# 2_matrix.net
KiCad netlist of a schematic drawn in Altium Designer
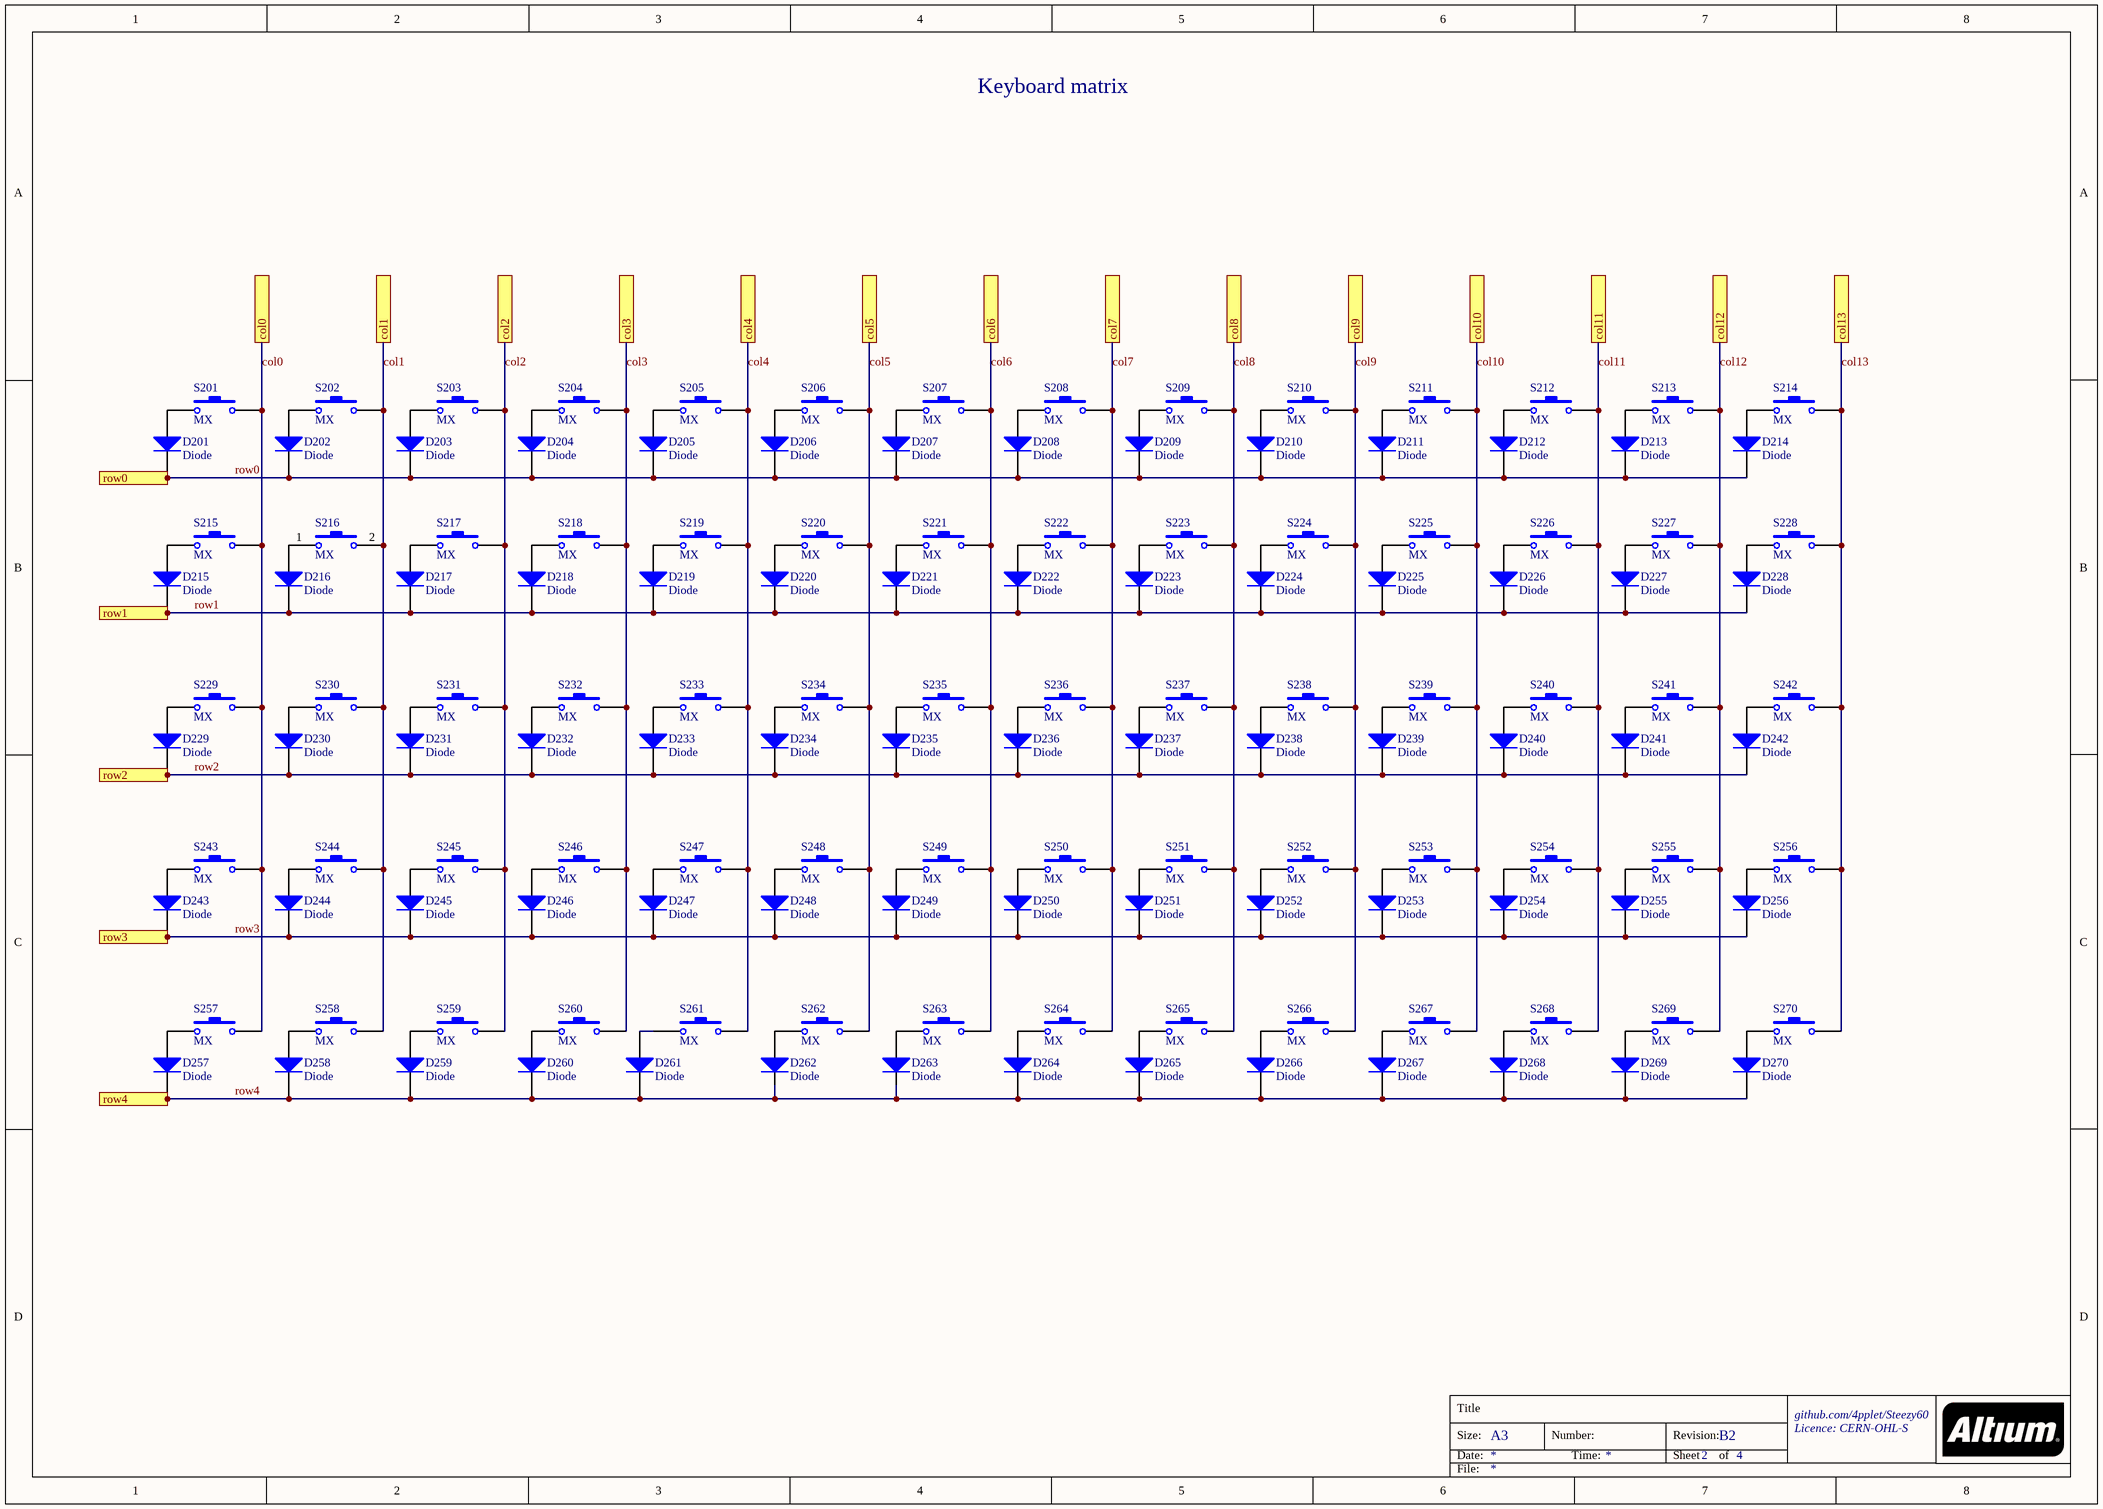
[diagram p0: 2_matrix.SchDoc]

(export (version "E")
  (design (tool "Eeschema 10.0.6"))
  (components
    (comp (ref "D201")
      (value "Diode")
      (footprint "SOD-123")
      (description "Default Diode")
      (fields (field (name "LCSC PART #") "C81598") (field (name "MRF.PART") "1N4148W"))
      (libsource (lib "Miscellaneous Devices") (part "Diode"))
    )
    (comp (ref "D202")
      (value "Diode")
      (footprint "SOD-123")
      (description "Default Diode")
      (fields (field (name "LCSC PART #") "C81598") (field (name "MRF.PART") "1N4148W"))
      (libsource (lib "Miscellaneous Devices") (part "Diode"))
    )
    (comp (ref "D203")
      (value "Diode")
      (footprint "SOD-123")
      (description "Default Diode")
      (fields (field (name "LCSC PART #") "C81598") (field (name "MRF.PART") "1N4148W"))
      (libsource (lib "Miscellaneous Devices") (part "Diode"))
    )
    (comp (ref "D204")
      (value "Diode")
      (footprint "SOD-123")
      (description "Default Diode")
      (fields (field (name "LCSC PART #") "C81598") (field (name "MRF.PART") "1N4148W"))
      (libsource (lib "Miscellaneous Devices") (part "Diode"))
    )
    (comp (ref "D205")
      (value "Diode")
      (footprint "SOD-123")
      (description "Default Diode")
      (fields (field (name "LCSC PART #") "C81598") (field (name "MRF.PART") "1N4148W"))
      (libsource (lib "Miscellaneous Devices") (part "Diode"))
    )
    (comp (ref "D206")
      (value "Diode")
      (footprint "SOD-123")
      (description "Default Diode")
      (fields (field (name "LCSC PART #") "C81598") (field (name "MRF.PART") "1N4148W"))
      (libsource (lib "Miscellaneous Devices") (part "Diode"))
    )
    (comp (ref "D207")
      (value "Diode")
      (footprint "SOD-123")
      (description "Default Diode")
      (fields (field (name "LCSC PART #") "C81598") (field (name "MRF.PART") "1N4148W"))
      (libsource (lib "Miscellaneous Devices") (part "Diode"))
    )
    (comp (ref "D208")
      (value "Diode")
      (footprint "SOD-123")
      (description "Default Diode")
      (fields (field (name "LCSC PART #") "C81598") (field (name "MRF.PART") "1N4148W"))
      (libsource (lib "Miscellaneous Devices") (part "Diode"))
    )
    (comp (ref "D209")
      (value "Diode")
      (footprint "SOD-123")
      (description "Default Diode")
      (fields (field (name "LCSC PART #") "C81598") (field (name "MRF.PART") "1N4148W"))
      (libsource (lib "Miscellaneous Devices") (part "Diode"))
    )
    (comp (ref "D210")
      (value "Diode")
      (footprint "SOD-123")
      (description "Default Diode")
      (fields (field (name "LCSC PART #") "C81598") (field (name "MRF.PART") "1N4148W"))
      (libsource (lib "Miscellaneous Devices") (part "Diode"))
    )
    (comp (ref "D211")
      (value "Diode")
      (footprint "SOD-123")
      (description "Default Diode")
      (fields (field (name "LCSC PART #") "C81598") (field (name "MRF.PART") "1N4148W"))
      (libsource (lib "Miscellaneous Devices") (part "Diode"))
    )
    (comp (ref "D212")
      (value "Diode")
      (footprint "SOD-123")
      (description "Default Diode")
      (fields (field (name "LCSC PART #") "C81598") (field (name "MRF.PART") "1N4148W"))
      (libsource (lib "Miscellaneous Devices") (part "Diode"))
    )
    (comp (ref "D213")
      (value "Diode")
      (footprint "SOD-123")
      (description "Default Diode")
      (fields (field (name "LCSC PART #") "C81598") (field (name "MRF.PART") "1N4148W"))
      (libsource (lib "Miscellaneous Devices") (part "Diode"))
    )
    (comp (ref "D214")
      (value "Diode")
      (footprint "SOD-123")
      (description "Default Diode")
      (fields (field (name "LCSC PART #") "C81598") (field (name "MRF.PART") "1N4148W"))
      (libsource (lib "Miscellaneous Devices") (part "Diode"))
    )
    (comp (ref "D215")
      (value "Diode")
      (footprint "SOD-123")
      (description "Default Diode")
      (fields (field (name "LCSC PART #") "C81598") (field (name "MRF.PART") "1N4148W"))
      (libsource (lib "Miscellaneous Devices") (part "Diode"))
    )
    (comp (ref "D216")
      (value "Diode")
      (footprint "SOD-123")
      (description "Default Diode")
      (fields (field (name "LCSC PART #") "C81598") (field (name "MRF.PART") "1N4148W"))
      (libsource (lib "Miscellaneous Devices") (part "Diode"))
    )
    (comp (ref "D217")
      (value "Diode")
      (footprint "SOD-123")
      (description "Default Diode")
      (fields (field (name "LCSC PART #") "C81598") (field (name "MRF.PART") "1N4148W"))
      (libsource (lib "Miscellaneous Devices") (part "Diode"))
    )
    (comp (ref "D218")
      (value "Diode")
      (footprint "SOD-123")
      (description "Default Diode")
      (fields (field (name "LCSC PART #") "C81598") (field (name "MRF.PART") "1N4148W"))
      (libsource (lib "Miscellaneous Devices") (part "Diode"))
    )
    (comp (ref "D219")
      (value "Diode")
      (footprint "SOD-123")
      (description "Default Diode")
      (fields (field (name "LCSC PART #") "C81598") (field (name "MRF.PART") "1N4148W"))
      (libsource (lib "Miscellaneous Devices") (part "Diode"))
    )
    (comp (ref "D220")
      (value "Diode")
      (footprint "SOD-123")
      (description "Default Diode")
      (fields (field (name "LCSC PART #") "C81598") (field (name "MRF.PART") "1N4148W"))
      (libsource (lib "Miscellaneous Devices") (part "Diode"))
    )
    (comp (ref "D221")
      (value "Diode")
      (footprint "SOD-123")
      (description "Default Diode")
      (fields (field (name "LCSC PART #") "C81598") (field (name "MRF.PART") "1N4148W"))
      (libsource (lib "Miscellaneous Devices") (part "Diode"))
    )
    (comp (ref "D222")
      (value "Diode")
      (footprint "SOD-123")
      (description "Default Diode")
      (fields (field (name "LCSC PART #") "C81598") (field (name "MRF.PART") "1N4148W"))
      (libsource (lib "Miscellaneous Devices") (part "Diode"))
    )
    (comp (ref "D223")
      (value "Diode")
      (footprint "SOD-123")
      (description "Default Diode")
      (fields (field (name "LCSC PART #") "C81598") (field (name "MRF.PART") "1N4148W"))
      (libsource (lib "Miscellaneous Devices") (part "Diode"))
    )
    (comp (ref "D224")
      (value "Diode")
      (footprint "SOD-123")
      (description "Default Diode")
      (fields (field (name "LCSC PART #") "C81598") (field (name "MRF.PART") "1N4148W"))
      (libsource (lib "Miscellaneous Devices") (part "Diode"))
    )
    (comp (ref "D225")
      (value "Diode")
      (footprint "SOD-123")
      (description "Default Diode")
      (fields (field (name "LCSC PART #") "C81598") (field (name "MRF.PART") "1N4148W"))
      (libsource (lib "Miscellaneous Devices") (part "Diode"))
    )
    (comp (ref "D226")
      (value "Diode")
      (footprint "SOD-123")
      (description "Default Diode")
      (fields (field (name "LCSC PART #") "C81598") (field (name "MRF.PART") "1N4148W"))
      (libsource (lib "Miscellaneous Devices") (part "Diode"))
    )
    (comp (ref "D227")
      (value "Diode")
      (footprint "SOD-123")
      (description "Default Diode")
      (fields (field (name "LCSC PART #") "C81598") (field (name "MRF.PART") "1N4148W"))
      (libsource (lib "Miscellaneous Devices") (part "Diode"))
    )
    (comp (ref "D228")
      (value "Diode")
      (footprint "SOD-123")
      (description "Default Diode")
      (fields (field (name "LCSC PART #") "C81598") (field (name "MRF.PART") "1N4148W"))
      (libsource (lib "Miscellaneous Devices") (part "Diode"))
    )
    (comp (ref "D229")
      (value "Diode")
      (footprint "SOD-123")
      (description "Default Diode")
      (fields (field (name "LCSC PART #") "C81598") (field (name "MRF.PART") "1N4148W"))
      (libsource (lib "Miscellaneous Devices") (part "Diode"))
    )
    (comp (ref "D230")
      (value "Diode")
      (footprint "SOD-123")
      (description "Default Diode")
      (fields (field (name "LCSC PART #") "C81598") (field (name "MRF.PART") "1N4148W"))
      (libsource (lib "Miscellaneous Devices") (part "Diode"))
    )
    (comp (ref "D231")
      (value "Diode")
      (footprint "SOD-123")
      (description "Default Diode")
      (fields (field (name "LCSC PART #") "C81598") (field (name "MRF.PART") "1N4148W"))
      (libsource (lib "Miscellaneous Devices") (part "Diode"))
    )
    (comp (ref "D232")
      (value "Diode")
      (footprint "SOD-123")
      (description "Default Diode")
      (fields (field (name "LCSC PART #") "C81598") (field (name "MRF.PART") "1N4148W"))
      (libsource (lib "Miscellaneous Devices") (part "Diode"))
    )
    (comp (ref "D233")
      (value "Diode")
      (footprint "SOD-123")
      (description "Default Diode")
      (fields (field (name "LCSC PART #") "C81598") (field (name "MRF.PART") "1N4148W"))
      (libsource (lib "Miscellaneous Devices") (part "Diode"))
    )
    (comp (ref "D234")
      (value "Diode")
      (footprint "SOD-123")
      (description "Default Diode")
      (fields (field (name "LCSC PART #") "C81598") (field (name "MRF.PART") "1N4148W"))
      (libsource (lib "Miscellaneous Devices") (part "Diode"))
    )
    (comp (ref "D235")
      (value "Diode")
      (footprint "SOD-123")
      (description "Default Diode")
      (fields (field (name "LCSC PART #") "C81598") (field (name "MRF.PART") "1N4148W"))
      (libsource (lib "Miscellaneous Devices") (part "Diode"))
    )
    (comp (ref "D236")
      (value "Diode")
      (footprint "SOD-123")
      (description "Default Diode")
      (fields (field (name "LCSC PART #") "C81598") (field (name "MRF.PART") "1N4148W"))
      (libsource (lib "Miscellaneous Devices") (part "Diode"))
    )
    (comp (ref "D237")
      (value "Diode")
      (footprint "SOD-123")
      (description "Default Diode")
      (fields (field (name "LCSC PART #") "C81598") (field (name "MRF.PART") "1N4148W"))
      (libsource (lib "Miscellaneous Devices") (part "Diode"))
    )
    (comp (ref "D238")
      (value "Diode")
      (footprint "SOD-123")
      (description "Default Diode")
      (fields (field (name "LCSC PART #") "C81598") (field (name "MRF.PART") "1N4148W"))
      (libsource (lib "Miscellaneous Devices") (part "Diode"))
    )
    (comp (ref "D239")
      (value "Diode")
      (footprint "SOD-123")
      (description "Default Diode")
      (fields (field (name "LCSC PART #") "C81598") (field (name "MRF.PART") "1N4148W"))
      (libsource (lib "Miscellaneous Devices") (part "Diode"))
    )
    (comp (ref "D240")
      (value "Diode")
      (footprint "SOD-123")
      (description "Default Diode")
      (fields (field (name "LCSC PART #") "C81598") (field (name "MRF.PART") "1N4148W"))
      (libsource (lib "Miscellaneous Devices") (part "Diode"))
    )
    (comp (ref "D241")
      (value "Diode")
      (footprint "SOD-123")
      (description "Default Diode")
      (fields (field (name "LCSC PART #") "C81598") (field (name "MRF.PART") "1N4148W"))
      (libsource (lib "Miscellaneous Devices") (part "Diode"))
    )
    (comp (ref "D242")
      (value "Diode")
      (footprint "SOD-123")
      (description "Default Diode")
      (fields (field (name "LCSC PART #") "C81598") (field (name "MRF.PART") "1N4148W"))
      (libsource (lib "Miscellaneous Devices") (part "Diode"))
    )
    (comp (ref "D243")
      (value "Diode")
      (footprint "SOD-123")
      (description "Default Diode")
      (fields (field (name "LCSC PART #") "C81598") (field (name "MRF.PART") "1N4148W"))
      (libsource (lib "Miscellaneous Devices") (part "Diode"))
    )
    (comp (ref "D244")
      (value "Diode")
      (footprint "SOD-123")
      (description "Default Diode")
      (fields (field (name "LCSC PART #") "C81598") (field (name "MRF.PART") "1N4148W"))
      (libsource (lib "Miscellaneous Devices") (part "Diode"))
    )
    (comp (ref "D245")
      (value "Diode")
      (footprint "SOD-123")
      (description "Default Diode")
      (fields (field (name "LCSC PART #") "C81598") (field (name "MRF.PART") "1N4148W"))
      (libsource (lib "Miscellaneous Devices") (part "Diode"))
    )
    (comp (ref "D246")
      (value "Diode")
      (footprint "SOD-123")
      (description "Default Diode")
      (fields (field (name "LCSC PART #") "C81598") (field (name "MRF.PART") "1N4148W"))
      (libsource (lib "Miscellaneous Devices") (part "Diode"))
    )
    (comp (ref "D247")
      (value "Diode")
      (footprint "SOD-123")
      (description "Default Diode")
      (fields (field (name "LCSC PART #") "C81598") (field (name "MRF.PART") "1N4148W"))
      (libsource (lib "Miscellaneous Devices") (part "Diode"))
    )
    (comp (ref "D248")
      (value "Diode")
      (footprint "SOD-123")
      (description "Default Diode")
      (fields (field (name "LCSC PART #") "C81598") (field (name "MRF.PART") "1N4148W"))
      (libsource (lib "Miscellaneous Devices") (part "Diode"))
    )
    (comp (ref "D249")
      (value "Diode")
      (footprint "SOD-123")
      (description "Default Diode")
      (fields (field (name "LCSC PART #") "C81598") (field (name "MRF.PART") "1N4148W"))
      (libsource (lib "Miscellaneous Devices") (part "Diode"))
    )
    (comp (ref "D250")
      (value "Diode")
      (footprint "SOD-123")
      (description "Default Diode")
      (fields (field (name "LCSC PART #") "C81598") (field (name "MRF.PART") "1N4148W"))
      (libsource (lib "Miscellaneous Devices") (part "Diode"))
    )
    (comp (ref "D251")
      (value "Diode")
      (footprint "SOD-123")
      (description "Default Diode")
      (fields (field (name "LCSC PART #") "C81598") (field (name "MRF.PART") "1N4148W"))
      (libsource (lib "Miscellaneous Devices") (part "Diode"))
    )
    (comp (ref "D252")
      (value "Diode")
      (footprint "SOD-123")
      (description "Default Diode")
      (fields (field (name "LCSC PART #") "C81598") (field (name "MRF.PART") "1N4148W"))
      (libsource (lib "Miscellaneous Devices") (part "Diode"))
    )
    (comp (ref "D253")
      (value "Diode")
      (footprint "SOD-123")
      (description "Default Diode")
      (fields (field (name "LCSC PART #") "C81598") (field (name "MRF.PART") "1N4148W"))
      (libsource (lib "Miscellaneous Devices") (part "Diode"))
    )
    (comp (ref "D254")
      (value "Diode")
      (footprint "SOD-123")
      (description "Default Diode")
      (fields (field (name "LCSC PART #") "C81598") (field (name "MRF.PART") "1N4148W"))
      (libsource (lib "Miscellaneous Devices") (part "Diode"))
    )
    (comp (ref "D255")
      (value "Diode")
      (footprint "SOD-123")
      (description "Default Diode")
      (fields (field (name "LCSC PART #") "C81598") (field (name "MRF.PART") "1N4148W"))
      (libsource (lib "Miscellaneous Devices") (part "Diode"))
    )
    (comp (ref "D256")
      (value "Diode")
      (footprint "SOD-123")
      (description "Default Diode")
      (fields (field (name "LCSC PART #") "C81598") (field (name "MRF.PART") "1N4148W"))
      (libsource (lib "Miscellaneous Devices") (part "Diode"))
    )
    (comp (ref "D257")
      (value "Diode")
      (footprint "SOD-123")
      (description "Default Diode")
      (fields (field (name "LCSC PART #") "C81598") (field (name "MRF.PART") "1N4148W"))
      (libsource (lib "Miscellaneous Devices") (part "Diode"))
    )
    (comp (ref "D258")
      (value "Diode")
      (footprint "SOD-123")
      (description "Default Diode")
      (fields (field (name "LCSC PART #") "C81598") (field (name "MRF.PART") "1N4148W"))
      (libsource (lib "Miscellaneous Devices") (part "Diode"))
    )
    (comp (ref "D259")
      (value "Diode")
      (footprint "SOD-123")
      (description "Default Diode")
      (fields (field (name "LCSC PART #") "C81598") (field (name "MRF.PART") "1N4148W"))
      (libsource (lib "Miscellaneous Devices") (part "Diode"))
    )
    (comp (ref "D260")
      (value "Diode")
      (footprint "SOD-123")
      (description "Default Diode")
      (fields (field (name "LCSC PART #") "C81598") (field (name "MRF.PART") "1N4148W"))
      (libsource (lib "Miscellaneous Devices") (part "Diode"))
    )
    (comp (ref "D261")
      (value "Diode")
      (footprint "SOD-123")
      (description "Default Diode")
      (fields (field (name "LCSC PART #") "C81598") (field (name "MRF.PART") "1N4148W"))
      (libsource (lib "Miscellaneous Devices") (part "Diode"))
    )
    (comp (ref "D262")
      (value "Diode")
      (footprint "SOD-123")
      (description "Default Diode")
      (fields (field (name "LCSC PART #") "C81598") (field (name "MRF.PART") "1N4148W"))
      (libsource (lib "Miscellaneous Devices") (part "Diode"))
    )
    (comp (ref "D263")
      (value "Diode")
      (footprint "SOD-123")
      (description "Default Diode")
      (fields (field (name "LCSC PART #") "C81598") (field (name "MRF.PART") "1N4148W"))
      (libsource (lib "Miscellaneous Devices") (part "Diode"))
    )
    (comp (ref "D264")
      (value "Diode")
      (footprint "SOD-123")
      (description "Default Diode")
      (fields (field (name "LCSC PART #") "C81598") (field (name "MRF.PART") "1N4148W"))
      (libsource (lib "Miscellaneous Devices") (part "Diode"))
    )
    (comp (ref "D265")
      (value "Diode")
      (footprint "SOD-123")
      (description "Default Diode")
      (fields (field (name "LCSC PART #") "C81598") (field (name "MRF.PART") "1N4148W"))
      (libsource (lib "Miscellaneous Devices") (part "Diode"))
    )
    (comp (ref "D266")
      (value "Diode")
      (footprint "SOD-123")
      (description "Default Diode")
      (fields (field (name "LCSC PART #") "C81598") (field (name "MRF.PART") "1N4148W"))
      (libsource (lib "Miscellaneous Devices") (part "Diode"))
    )
    (comp (ref "D267")
      (value "Diode")
      (footprint "SOD-123")
      (description "Default Diode")
      (fields (field (name "LCSC PART #") "C81598") (field (name "MRF.PART") "1N4148W"))
      (libsource (lib "Miscellaneous Devices") (part "Diode"))
    )
    (comp (ref "D268")
      (value "Diode")
      (footprint "SOD-123")
      (description "Default Diode")
      (fields (field (name "LCSC PART #") "C81598") (field (name "MRF.PART") "1N4148W"))
      (libsource (lib "Miscellaneous Devices") (part "Diode"))
    )
    (comp (ref "D269")
      (value "Diode")
      (footprint "SOD-123")
      (description "Default Diode")
      (fields (field (name "LCSC PART #") "C81598") (field (name "MRF.PART") "1N4148W"))
      (libsource (lib "Miscellaneous Devices") (part "Diode"))
    )
    (comp (ref "D270")
      (value "Diode")
      (footprint "SOD-123")
      (description "Default Diode")
      (fields (field (name "LCSC PART #") "C81598") (field (name "MRF.PART") "1N4148W"))
      (libsource (lib "Miscellaneous Devices") (part "Diode"))
    )
    (comp (ref "S201")
      (value "MX")
      (footprint "Alps-switch - switched pol")
      (description "Switch")
      (libsource (lib "Miscellaneous Devices") (part "SW-PB"))
    )
    (comp (ref "S202")
      (value "MX")
      (footprint "Alps-switch - switched pol")
      (description "Switch")
      (libsource (lib "Miscellaneous Devices") (part "SW-PB"))
    )
    (comp (ref "S203")
      (value "MX")
      (footprint "Alps-switch - switched pol")
      (description "Switch")
      (libsource (lib "Miscellaneous Devices") (part "SW-PB"))
    )
    (comp (ref "S204")
      (value "MX")
      (footprint "Alps-switch - switched pol")
      (description "Switch")
      (libsource (lib "Miscellaneous Devices") (part "SW-PB"))
    )
    (comp (ref "S205")
      (value "MX")
      (footprint "Alps-switch - switched pol")
      (description "Switch")
      (libsource (lib "Miscellaneous Devices") (part "SW-PB"))
    )
    (comp (ref "S206")
      (value "MX")
      (footprint "Alps-switch - switched pol")
      (description "Switch")
      (libsource (lib "Miscellaneous Devices") (part "SW-PB"))
    )
    (comp (ref "S207")
      (value "MX")
      (footprint "Alps-switch - switched pol")
      (description "Switch")
      (libsource (lib "Miscellaneous Devices") (part "SW-PB"))
    )
    (comp (ref "S208")
      (value "MX")
      (footprint "Alps-switch - switched pol")
      (description "Switch")
      (libsource (lib "Miscellaneous Devices") (part "SW-PB"))
    )
    (comp (ref "S209")
      (value "MX")
      (footprint "Alps-switch")
      (description "Switch")
      (libsource (lib "Miscellaneous Devices") (part "SW-PB"))
    )
    (comp (ref "S210")
      (value "MX")
      (footprint "Alps-switch")
      (description "Switch")
      (libsource (lib "Miscellaneous Devices") (part "SW-PB"))
    )
    (comp (ref "S211")
      (value "MX")
      (footprint "Alps-switch")
      (description "Switch")
      (libsource (lib "Miscellaneous Devices") (part "SW-PB"))
    )
    (comp (ref "S212")
      (value "MX")
      (footprint "Alps-switch")
      (description "Switch")
      (libsource (lib "Miscellaneous Devices") (part "SW-PB"))
    )
    (comp (ref "S213")
      (value "MX")
      (footprint "Alps-switch")
      (description "Switch")
      (libsource (lib "Miscellaneous Devices") (part "SW-PB"))
    )
    (comp (ref "S214")
      (value "MX")
      (footprint "ALPS-SWITCH - FLAT PIN1")
      (description "Switch")
      (libsource (lib "Miscellaneous Devices") (part "SW-PB"))
    )
    (comp (ref "S215")
      (value "MX")
      (footprint "ALPS-switch - 1.25U - switched pol")
      (description "TAB")
      (libsource (lib "Miscellaneous Devices") (part "SW-PB"))
    )
    (comp (ref "S216")
      (value "MX")
      (footprint "Alps-switch")
      (description "Switch")
      (libsource (lib "") (part "SW-PB_1"))
    )
    (comp (ref "S217")
      (value "MX")
      (footprint "Alps-switch - switched pol")
      (description "Switch")
      (libsource (lib "Miscellaneous Devices") (part "SW-PB"))
    )
    (comp (ref "S218")
      (value "MX")
      (footprint "Alps-switch - switched pol")
      (description "Switch")
      (libsource (lib "Miscellaneous Devices") (part "SW-PB"))
    )
    (comp (ref "S219")
      (value "MX")
      (footprint "Alps-switch - switched pol")
      (description "Switch")
      (libsource (lib "Miscellaneous Devices") (part "SW-PB"))
    )
    (comp (ref "S220")
      (value "MX")
      (footprint "Alps-switch - switched pol")
      (description "Switch")
      (libsource (lib "Miscellaneous Devices") (part "SW-PB"))
    )
    (comp (ref "S221")
      (value "MX")
      (footprint "Alps-switch - switched pol")
      (description "Switch")
      (libsource (lib "Miscellaneous Devices") (part "SW-PB"))
    )
    (comp (ref "S222")
      (value "MX")
      (footprint "Alps-switch - switched pol")
      (description "Switch")
      (libsource (lib "Miscellaneous Devices") (part "SW-PB"))
    )
    (comp (ref "S223")
      (value "MX")
      (footprint "Alps-switch - switched pol")
      (description "Switch")
      (libsource (lib "Miscellaneous Devices") (part "SW-PB"))
    )
    (comp (ref "S224")
      (value "MX")
      (footprint "Alps-switch - switched pol")
      (description "Switch")
      (libsource (lib "Miscellaneous Devices") (part "SW-PB"))
    )
    (comp (ref "S225")
      (value "MX")
      (footprint "Alps-switch")
      (description "Switch")
      (libsource (lib "Miscellaneous Devices") (part "SW-PB"))
    )
    (comp (ref "S226")
      (value "MX")
      (footprint "Alps-switch")
      (description "Switch")
      (libsource (lib "Miscellaneous Devices") (part "SW-PB"))
    )
    (comp (ref "S227")
      (value "MX")
      (footprint "ALPS-switch - offset-R")
      (description "Switch")
      (libsource (lib "Miscellaneous Devices") (part "SW-PB"))
    )
    (comp (ref "S228")
      (value "MX")
      (footprint "ALPS-switch - 1.5U")
      (description "Switch")
      (libsource (lib "Miscellaneous Devices") (part "SW-PB"))
    )
    (comp (ref "S229")
      (value "MX")
      (footprint "ALPS-switch - CAPS")
      (description "Switch")
      (libsource (lib "Miscellaneous Devices") (part "SW-PB"))
    )
    (comp (ref "S230")
      (value "MX")
      (footprint "Alps-switch")
      (description "Switch")
      (libsource (lib "Miscellaneous Devices") (part "SW-PB"))
    )
    (comp (ref "S231")
      (value "MX")
      (footprint "Alps-switch - switched pol")
      (description "Switch")
      (libsource (lib "Miscellaneous Devices") (part "SW-PB"))
    )
    (comp (ref "S232")
      (value "MX")
      (footprint "Alps-switch - switched pol")
      (description "Switch")
      (libsource (lib "Miscellaneous Devices") (part "SW-PB"))
    )
    (comp (ref "S233")
      (value "MX")
      (footprint "Alps-switch - switched pol")
      (description "Switch")
      (libsource (lib "Miscellaneous Devices") (part "SW-PB"))
    )
    (comp (ref "S234")
      (value "MX")
      (footprint "Alps-switch - switched pol")
      (description "Switch")
      (libsource (lib "Miscellaneous Devices") (part "SW-PB"))
    )
    (comp (ref "S235")
      (value "MX")
      (footprint "Alps-switch - switched pol")
      (description "Switch")
      (libsource (lib "Miscellaneous Devices") (part "SW-PB"))
    )
    (comp (ref "S236")
      (value "MX")
      (footprint "Alps-switch - switched pol")
      (description "Switch")
      (libsource (lib "Miscellaneous Devices") (part "SW-PB"))
    )
    (comp (ref "S237")
      (value "MX")
      (footprint "Alps-switch - switched pol")
      (description "Switch")
      (libsource (lib "Miscellaneous Devices") (part "SW-PB"))
    )
    (comp (ref "S238")
      (value "MX")
      (footprint "Alps-switch - switched pol")
      (description "Switch")
      (libsource (lib "Miscellaneous Devices") (part "SW-PB"))
    )
    (comp (ref "S239")
      (value "MX")
      (footprint "Alps-switch")
      (description "Switch")
      (libsource (lib "Miscellaneous Devices") (part "SW-PB"))
    )
    (comp (ref "S240")
      (value "MX")
      (footprint "Alps-switch")
      (description "Switch")
      (libsource (lib "Miscellaneous Devices") (part "SW-PB"))
    )
    (comp (ref "S241")
      (value "MX")
      (footprint "Alps-switch - switched pol")
      (description "Switch")
      (libsource (lib "Miscellaneous Devices") (part "SW-PB"))
    )
    (comp (ref "S242")
      (value "MX")
      (footprint "ALPS-switch - Enter - rotated stab")
      (description "Switch")
      (libsource (lib "Miscellaneous Devices") (part "SW-PB"))
    )
    (comp (ref "S243")
      (value "MX")
      (footprint "ALPS-switch - Left shift")
      (description "Switch")
      (libsource (lib "Miscellaneous Devices") (part "SW-PB"))
    )
    (comp (ref "S244")
      (value "MX")
      (footprint "ALPS-switch - smalleroffset-R")
      (description "Switch")
      (libsource (lib "Miscellaneous Devices") (part "SW-PB"))
    )
    (comp (ref "S245")
      (value "MX")
      (footprint "ALPS-switch - offset")
      (description "Switch")
      (libsource (lib "Miscellaneous Devices") (part "SW-PB"))
    )
    (comp (ref "S246")
      (value "MX")
      (footprint "ALPS-switch - offset")
      (description "Switch")
      (libsource (lib "Miscellaneous Devices") (part "SW-PB"))
    )
    (comp (ref "S247")
      (value "MX")
      (footprint "ALPS-switch - offset")
      (description "Switch")
      (libsource (lib "Miscellaneous Devices") (part "SW-PB"))
    )
    (comp (ref "S248")
      (value "MX")
      (footprint "ALPS-switch - offset")
      (description "Switch")
      (libsource (lib "Miscellaneous Devices") (part "SW-PB"))
    )
    (comp (ref "S249")
      (value "MX")
      (footprint "ALPS-switch - offset")
      (description "Switch")
      (libsource (lib "Miscellaneous Devices") (part "SW-PB"))
    )
    (comp (ref "S250")
      (value "MX")
      (footprint "ALPS-switch - offset")
      (description "Switch")
      (libsource (lib "Miscellaneous Devices") (part "SW-PB"))
    )
    (comp (ref "S251")
      (value "MX")
      (footprint "ALPS-switch - offset")
      (description "Switch")
      (libsource (lib "Miscellaneous Devices") (part "SW-PB"))
    )
    (comp (ref "S252")
      (value "MX")
      (footprint "ALPS-switch - offset")
      (description "Switch")
      (libsource (lib "Miscellaneous Devices") (part "SW-PB"))
    )
    (comp (ref "S253")
      (value "MX")
      (footprint "ALPS-switch - offset")
      (description "Switch")
      (libsource (lib "Miscellaneous Devices") (part "SW-PB"))
    )
    (comp (ref "S254")
      (value "MX")
      (footprint "ALPS-switch - offset")
      (description "Switch")
      (libsource (lib "Miscellaneous Devices") (part "SW-PB"))
    )
    (comp (ref "S255")
      (value "MX")
      (footprint "ALPS-SWITCH - CRAZY SHIFT")
      (description "Switch")
      (libsource (lib "Miscellaneous Devices") (part "SW-PB"))
    )
    (comp (ref "S256")
      (value "MX")
      (footprint "ALPS-switch - right shift")
      (description "Switch")
      (libsource (lib "Miscellaneous Devices") (part "SW-PB"))
    )
    (comp (ref "S257")
      (value "MX")
      (footprint "ALPS-switch - L_CTRL")
      (description "Switch")
      (libsource (lib "Miscellaneous Devices") (part "SW-PB"))
    )
    (comp (ref "S258")
      (value "MX")
      (footprint "ALPS-switch - L_WIN")
      (description "Switch")
      (libsource (lib "Miscellaneous Devices") (part "SW-PB"))
    )
    (comp (ref "S259")
      (value "MX")
      (footprint "Alps-switch")
      (description "Switch")
      (libsource (lib "Miscellaneous Devices") (part "SW-PB"))
    )
    (comp (ref "S260")
      (value "MX")
      (footprint "ALPS-switch - L_alt")
      (description "Switch")
      (libsource (lib "Miscellaneous Devices") (part "SW-PB"))
    )
    (comp (ref "S261")
      (value "MX")
      (footprint "ALPS-switch - L split space")
      (description "Switch")
      (libsource (lib "Miscellaneous Devices") (part "SW-PB"))
    )
    (comp (ref "S262")
      (value "MX")
      (footprint "ALPS-switch - Space")
      (description "Switch")
      (libsource (lib "Miscellaneous Devices") (part "SW-PB"))
    )
    (comp (ref "S263")
      (value "MX")
      (footprint "ALPS-switch - R split space")
      (description "Switch")
      (libsource (lib "Miscellaneous Devices") (part "SW-PB"))
    )
    (comp (ref "S264")
      (value "MX")
      (footprint "ALPS-switch - R PN")
      (description "Switch")
      (libsource (lib "Miscellaneous Devices") (part "SW-PB"))
    )
    (comp (ref "S265")
      (value "MX")
      (footprint "ALPS-switch - R_alt")
      (description "Switch")
      (libsource (lib "Miscellaneous Devices") (part "SW-PB"))
    )
    (comp (ref "S266")
      (value "MX")
      (footprint "Alps-switch")
      (description "Switch")
      (libsource (lib "Miscellaneous Devices") (part "SW-PB"))
    )
    (comp (ref "S267")
      (value "MX")
      (footprint "ALPS-switch - R_WIN")
      (description "Switch")
      (libsource (lib "Miscellaneous Devices") (part "SW-PB"))
    )
    (comp (ref "S268")
      (value "MX")
      (footprint "ALPS-switch - R_CTRL")
      (description "Switch")
      (libsource (lib "Miscellaneous Devices") (part "SW-PB"))
    )
    (comp (ref "S269")
      (value "MX")
      (footprint "Alps-switch - fn and shift")
      (description "Switch")
      (libsource (lib "Miscellaneous Devices") (part "SW-PB"))
    )
    (comp (ref "S270")
      (value "MX")
      (footprint "ALPS-switch - backspace")
      (description "Switch")
      (libsource (lib "Miscellaneous Devices") (part "SW-PB"))
    )
  )
  (nets
    (net (code "1") (name "/col0") (class "Default")
      (node (ref "S201") (pin "2") (pinfunction "2_2") (pintype "passive"))
      (node (ref "S215") (pin "2") (pinfunction "2_2") (pintype "passive"))
      (node (ref "S229") (pin "2") (pinfunction "2_2") (pintype "passive"))
      (node (ref "S243") (pin "2") (pinfunction "2_2") (pintype "passive"))
      (node (ref "S257") (pin "2") (pinfunction "2_2") (pintype "passive"))
    )
    (net (code "2") (name "/col1") (class "Default")
      (node (ref "S202") (pin "2") (pinfunction "2_2") (pintype "passive"))
      (node (ref "S216") (pin "2") (pinfunction "2_2") (pintype "passive"))
      (node (ref "S230") (pin "2") (pinfunction "2_2") (pintype "passive"))
      (node (ref "S244") (pin "2") (pinfunction "2_2") (pintype "passive"))
      (node (ref "S258") (pin "2") (pinfunction "2_2") (pintype "passive"))
    )
    (net (code "3") (name "/col2") (class "Default")
      (node (ref "S203") (pin "2") (pinfunction "2_2") (pintype "passive"))
      (node (ref "S217") (pin "2") (pinfunction "2_2") (pintype "passive"))
      (node (ref "S231") (pin "2") (pinfunction "2_2") (pintype "passive"))
      (node (ref "S245") (pin "2") (pinfunction "2_2") (pintype "passive"))
      (node (ref "S259") (pin "2") (pinfunction "2_2") (pintype "passive"))
    )
    (net (code "4") (name "/col3") (class "Default")
      (node (ref "S204") (pin "2") (pinfunction "2_2") (pintype "passive"))
      (node (ref "S218") (pin "2") (pinfunction "2_2") (pintype "passive"))
      (node (ref "S232") (pin "2") (pinfunction "2_2") (pintype "passive"))
      (node (ref "S246") (pin "2") (pinfunction "2_2") (pintype "passive"))
      (node (ref "S260") (pin "2") (pinfunction "2_2") (pintype "passive"))
    )
    (net (code "5") (name "/col4") (class "Default")
      (node (ref "S205") (pin "2") (pinfunction "2_2") (pintype "passive"))
      (node (ref "S219") (pin "2") (pinfunction "2_2") (pintype "passive"))
      (node (ref "S233") (pin "2") (pinfunction "2_2") (pintype "passive"))
      (node (ref "S247") (pin "2") (pinfunction "2_2") (pintype "passive"))
      (node (ref "S261") (pin "2") (pinfunction "2_2") (pintype "passive"))
    )
    (net (code "6") (name "/col5") (class "Default")
      (node (ref "S206") (pin "2") (pinfunction "2_2") (pintype "passive"))
      (node (ref "S220") (pin "2") (pinfunction "2_2") (pintype "passive"))
      (node (ref "S234") (pin "2") (pinfunction "2_2") (pintype "passive"))
      (node (ref "S248") (pin "2") (pinfunction "2_2") (pintype "passive"))
      (node (ref "S262") (pin "2") (pinfunction "2_2") (pintype "passive"))
    )
    (net (code "7") (name "/col6") (class "Default")
      (node (ref "S207") (pin "2") (pinfunction "2_2") (pintype "passive"))
      (node (ref "S221") (pin "2") (pinfunction "2_2") (pintype "passive"))
      (node (ref "S235") (pin "2") (pinfunction "2_2") (pintype "passive"))
      (node (ref "S249") (pin "2") (pinfunction "2_2") (pintype "passive"))
      (node (ref "S263") (pin "2") (pinfunction "2_2") (pintype "passive"))
    )
    (net (code "8") (name "/col7") (class "Default")
      (node (ref "S208") (pin "2") (pinfunction "2_2") (pintype "passive"))
      (node (ref "S222") (pin "2") (pinfunction "2_2") (pintype "passive"))
      (node (ref "S236") (pin "2") (pinfunction "2_2") (pintype "passive"))
      (node (ref "S250") (pin "2") (pinfunction "2_2") (pintype "passive"))
      (node (ref "S264") (pin "2") (pinfunction "2_2") (pintype "passive"))
    )
    (net (code "9") (name "/col8") (class "Default")
      (node (ref "S209") (pin "2") (pinfunction "2_2") (pintype "passive"))
      (node (ref "S223") (pin "2") (pinfunction "2_2") (pintype "passive"))
      (node (ref "S237") (pin "2") (pinfunction "2_2") (pintype "passive"))
      (node (ref "S251") (pin "2") (pinfunction "2_2") (pintype "passive"))
      (node (ref "S265") (pin "2") (pinfunction "2_2") (pintype "passive"))
    )
    (net (code "10") (name "/col9") (class "Default")
      (node (ref "S210") (pin "2") (pinfunction "2_2") (pintype "passive"))
      (node (ref "S224") (pin "2") (pinfunction "2_2") (pintype "passive"))
      (node (ref "S238") (pin "2") (pinfunction "2_2") (pintype "passive"))
      (node (ref "S252") (pin "2") (pinfunction "2_2") (pintype "passive"))
      (node (ref "S266") (pin "2") (pinfunction "2_2") (pintype "passive"))
    )
    (net (code "11") (name "/col10") (class "Default")
      (node (ref "S211") (pin "2") (pinfunction "2_2") (pintype "passive"))
      (node (ref "S225") (pin "2") (pinfunction "2_2") (pintype "passive"))
      (node (ref "S239") (pin "2") (pinfunction "2_2") (pintype "passive"))
      (node (ref "S253") (pin "2") (pinfunction "2_2") (pintype "passive"))
      (node (ref "S267") (pin "2") (pinfunction "2_2") (pintype "passive"))
    )
    (net (code "12") (name "/col11") (class "Default")
      (node (ref "S212") (pin "2") (pinfunction "2_2") (pintype "passive"))
      (node (ref "S226") (pin "2") (pinfunction "2_2") (pintype "passive"))
      (node (ref "S240") (pin "2") (pinfunction "2_2") (pintype "passive"))
      (node (ref "S254") (pin "2") (pinfunction "2_2") (pintype "passive"))
      (node (ref "S268") (pin "2") (pinfunction "2_2") (pintype "passive"))
    )
    (net (code "13") (name "/col12") (class "Default")
      (node (ref "S213") (pin "2") (pinfunction "2_2") (pintype "passive"))
      (node (ref "S227") (pin "2") (pinfunction "2_2") (pintype "passive"))
      (node (ref "S241") (pin "2") (pinfunction "2_2") (pintype "passive"))
      (node (ref "S255") (pin "2") (pinfunction "2_2") (pintype "passive"))
      (node (ref "S269") (pin "2") (pinfunction "2_2") (pintype "passive"))
    )
    (net (code "14") (name "/col13") (class "Default")
      (node (ref "S214") (pin "2") (pinfunction "2_2") (pintype "passive"))
      (node (ref "S228") (pin "2") (pinfunction "2_2") (pintype "passive"))
      (node (ref "S242") (pin "2") (pinfunction "2_2") (pintype "passive"))
      (node (ref "S256") (pin "2") (pinfunction "2_2") (pintype "passive"))
      (node (ref "S270") (pin "2") (pinfunction "2_2") (pintype "passive"))
    )
    (net (code "15") (name "/row0") (class "Default")
      (node (ref "D201") (pin "2") (pinfunction "K_2") (pintype "passive"))
      (node (ref "D202") (pin "2") (pinfunction "K_2") (pintype "passive"))
      (node (ref "D203") (pin "2") (pinfunction "K_2") (pintype "passive"))
      (node (ref "D204") (pin "2") (pinfunction "K_2") (pintype "passive"))
      (node (ref "D205") (pin "2") (pinfunction "K_2") (pintype "passive"))
      (node (ref "D206") (pin "2") (pinfunction "K_2") (pintype "passive"))
      (node (ref "D207") (pin "2") (pinfunction "K_2") (pintype "passive"))
      (node (ref "D208") (pin "2") (pinfunction "K_2") (pintype "passive"))
      (node (ref "D209") (pin "2") (pinfunction "K_2") (pintype "passive"))
      (node (ref "D210") (pin "2") (pinfunction "K_2") (pintype "passive"))
      (node (ref "D211") (pin "2") (pinfunction "K_2") (pintype "passive"))
      (node (ref "D212") (pin "2") (pinfunction "K_2") (pintype "passive"))
      (node (ref "D213") (pin "2") (pinfunction "K_2") (pintype "passive"))
      (node (ref "D214") (pin "2") (pinfunction "K_2") (pintype "passive"))
    )
    (net (code "16") (name "/row1") (class "Default")
      (node (ref "D215") (pin "2") (pinfunction "K_2") (pintype "passive"))
      (node (ref "D216") (pin "2") (pinfunction "K_2") (pintype "passive"))
      (node (ref "D217") (pin "2") (pinfunction "K_2") (pintype "passive"))
      (node (ref "D218") (pin "2") (pinfunction "K_2") (pintype "passive"))
      (node (ref "D219") (pin "2") (pinfunction "K_2") (pintype "passive"))
      (node (ref "D220") (pin "2") (pinfunction "K_2") (pintype "passive"))
      (node (ref "D221") (pin "2") (pinfunction "K_2") (pintype "passive"))
      (node (ref "D222") (pin "2") (pinfunction "K_2") (pintype "passive"))
      (node (ref "D223") (pin "2") (pinfunction "K_2") (pintype "passive"))
      (node (ref "D224") (pin "2") (pinfunction "K_2") (pintype "passive"))
      (node (ref "D225") (pin "2") (pinfunction "K_2") (pintype "passive"))
      (node (ref "D226") (pin "2") (pinfunction "K_2") (pintype "passive"))
      (node (ref "D227") (pin "2") (pinfunction "K_2") (pintype "passive"))
      (node (ref "D228") (pin "2") (pinfunction "K_2") (pintype "passive"))
    )
    (net (code "17") (name "/row2") (class "Default")
      (node (ref "D229") (pin "2") (pinfunction "K_2") (pintype "passive"))
      (node (ref "D230") (pin "2") (pinfunction "K_2") (pintype "passive"))
      (node (ref "D231") (pin "2") (pinfunction "K_2") (pintype "passive"))
      (node (ref "D232") (pin "2") (pinfunction "K_2") (pintype "passive"))
      (node (ref "D233") (pin "2") (pinfunction "K_2") (pintype "passive"))
      (node (ref "D234") (pin "2") (pinfunction "K_2") (pintype "passive"))
      (node (ref "D235") (pin "2") (pinfunction "K_2") (pintype "passive"))
      (node (ref "D236") (pin "2") (pinfunction "K_2") (pintype "passive"))
      (node (ref "D237") (pin "2") (pinfunction "K_2") (pintype "passive"))
      (node (ref "D238") (pin "2") (pinfunction "K_2") (pintype "passive"))
      (node (ref "D239") (pin "2") (pinfunction "K_2") (pintype "passive"))
      (node (ref "D240") (pin "2") (pinfunction "K_2") (pintype "passive"))
      (node (ref "D241") (pin "2") (pinfunction "K_2") (pintype "passive"))
      (node (ref "D242") (pin "2") (pinfunction "K_2") (pintype "passive"))
    )
    (net (code "18") (name "/row3") (class "Default")
      (node (ref "D243") (pin "2") (pinfunction "K_2") (pintype "passive"))
      (node (ref "D244") (pin "2") (pinfunction "K_2") (pintype "passive"))
      (node (ref "D245") (pin "2") (pinfunction "K_2") (pintype "passive"))
      (node (ref "D246") (pin "2") (pinfunction "K_2") (pintype "passive"))
      (node (ref "D247") (pin "2") (pinfunction "K_2") (pintype "passive"))
      (node (ref "D248") (pin "2") (pinfunction "K_2") (pintype "passive"))
      (node (ref "D249") (pin "2") (pinfunction "K_2") (pintype "passive"))
      (node (ref "D250") (pin "2") (pinfunction "K_2") (pintype "passive"))
      (node (ref "D251") (pin "2") (pinfunction "K_2") (pintype "passive"))
      (node (ref "D252") (pin "2") (pinfunction "K_2") (pintype "passive"))
      (node (ref "D253") (pin "2") (pinfunction "K_2") (pintype "passive"))
      (node (ref "D254") (pin "2") (pinfunction "K_2") (pintype "passive"))
      (node (ref "D255") (pin "2") (pinfunction "K_2") (pintype "passive"))
      (node (ref "D256") (pin "2") (pinfunction "K_2") (pintype "passive"))
    )
    (net (code "19") (name "/row4") (class "Default")
      (node (ref "D257") (pin "2") (pinfunction "K_2") (pintype "passive"))
      (node (ref "D258") (pin "2") (pinfunction "K_2") (pintype "passive"))
      (node (ref "D259") (pin "2") (pinfunction "K_2") (pintype "passive"))
      (node (ref "D260") (pin "2") (pinfunction "K_2") (pintype "passive"))
      (node (ref "D261") (pin "2") (pinfunction "K_2") (pintype "passive"))
      (node (ref "D262") (pin "2") (pinfunction "K_2") (pintype "passive"))
      (node (ref "D263") (pin "2") (pinfunction "K_2") (pintype "passive"))
      (node (ref "D264") (pin "2") (pinfunction "K_2") (pintype "passive"))
      (node (ref "D265") (pin "2") (pinfunction "K_2") (pintype "passive"))
      (node (ref "D266") (pin "2") (pinfunction "K_2") (pintype "passive"))
      (node (ref "D267") (pin "2") (pinfunction "K_2") (pintype "passive"))
      (node (ref "D268") (pin "2") (pinfunction "K_2") (pintype "passive"))
      (node (ref "D269") (pin "2") (pinfunction "K_2") (pintype "passive"))
      (node (ref "D270") (pin "2") (pinfunction "K_2") (pintype "passive"))
    )
    (net (code "20") (name "Net-(D201-A)") (class "Default")
      (node (ref "D201") (pin "1") (pinfunction "A_1") (pintype "passive"))
      (node (ref "S201") (pin "1") (pinfunction "1_1") (pintype "passive"))
    )
    (net (code "21") (name "Net-(D202-A)") (class "Default")
      (node (ref "D202") (pin "1") (pinfunction "A_1") (pintype "passive"))
      (node (ref "S202") (pin "1") (pinfunction "1_1") (pintype "passive"))
    )
    (net (code "22") (name "Net-(D203-A)") (class "Default")
      (node (ref "D203") (pin "1") (pinfunction "A_1") (pintype "passive"))
      (node (ref "S203") (pin "1") (pinfunction "1_1") (pintype "passive"))
    )
    (net (code "23") (name "Net-(D204-A)") (class "Default")
      (node (ref "D204") (pin "1") (pinfunction "A_1") (pintype "passive"))
      (node (ref "S204") (pin "1") (pinfunction "1_1") (pintype "passive"))
    )
    (net (code "24") (name "Net-(D205-A)") (class "Default")
      (node (ref "D205") (pin "1") (pinfunction "A_1") (pintype "passive"))
      (node (ref "S205") (pin "1") (pinfunction "1_1") (pintype "passive"))
    )
    (net (code "25") (name "Net-(D206-A)") (class "Default")
      (node (ref "D206") (pin "1") (pinfunction "A_1") (pintype "passive"))
      (node (ref "S206") (pin "1") (pinfunction "1_1") (pintype "passive"))
    )
    (net (code "26") (name "Net-(D207-A)") (class "Default")
      (node (ref "D207") (pin "1") (pinfunction "A_1") (pintype "passive"))
      (node (ref "S207") (pin "1") (pinfunction "1_1") (pintype "passive"))
    )
    (net (code "27") (name "Net-(D208-A)") (class "Default")
      (node (ref "D208") (pin "1") (pinfunction "A_1") (pintype "passive"))
      (node (ref "S208") (pin "1") (pinfunction "1_1") (pintype "passive"))
    )
    (net (code "28") (name "Net-(D209-A)") (class "Default")
      (node (ref "D209") (pin "1") (pinfunction "A_1") (pintype "passive"))
      (node (ref "S209") (pin "1") (pinfunction "1_1") (pintype "passive"))
    )
    (net (code "29") (name "Net-(D210-A)") (class "Default")
      (node (ref "D210") (pin "1") (pinfunction "A_1") (pintype "passive"))
      (node (ref "S210") (pin "1") (pinfunction "1_1") (pintype "passive"))
    )
    (net (code "30") (name "Net-(D211-A)") (class "Default")
      (node (ref "D211") (pin "1") (pinfunction "A_1") (pintype "passive"))
      (node (ref "S211") (pin "1") (pinfunction "1_1") (pintype "passive"))
    )
    (net (code "31") (name "Net-(D212-A)") (class "Default")
      (node (ref "D212") (pin "1") (pinfunction "A_1") (pintype "passive"))
      (node (ref "S212") (pin "1") (pinfunction "1_1") (pintype "passive"))
    )
    (net (code "32") (name "Net-(D213-A)") (class "Default")
      (node (ref "D213") (pin "1") (pinfunction "A_1") (pintype "passive"))
      (node (ref "S213") (pin "1") (pinfunction "1_1") (pintype "passive"))
    )
    (net (code "33") (name "Net-(D214-A)") (class "Default")
      (node (ref "D214") (pin "1") (pinfunction "A_1") (pintype "passive"))
      (node (ref "S214") (pin "1") (pinfunction "1_1") (pintype "passive"))
    )
    (net (code "34") (name "Net-(D215-A)") (class "Default")
      (node (ref "D215") (pin "1") (pinfunction "A_1") (pintype "passive"))
      (node (ref "S215") (pin "1") (pinfunction "1_1") (pintype "passive"))
    )
    (net (code "35") (name "Net-(D216-A)") (class "Default")
      (node (ref "D216") (pin "1") (pinfunction "A_1") (pintype "passive"))
      (node (ref "S216") (pin "1") (pinfunction "1_1") (pintype "passive"))
    )
    (net (code "36") (name "Net-(D217-A)") (class "Default")
      (node (ref "D217") (pin "1") (pinfunction "A_1") (pintype "passive"))
      (node (ref "S217") (pin "1") (pinfunction "1_1") (pintype "passive"))
    )
    (net (code "37") (name "Net-(D218-A)") (class "Default")
      (node (ref "D218") (pin "1") (pinfunction "A_1") (pintype "passive"))
      (node (ref "S218") (pin "1") (pinfunction "1_1") (pintype "passive"))
    )
    (net (code "38") (name "Net-(D219-A)") (class "Default")
      (node (ref "D219") (pin "1") (pinfunction "A_1") (pintype "passive"))
      (node (ref "S219") (pin "1") (pinfunction "1_1") (pintype "passive"))
    )
    (net (code "39") (name "Net-(D220-A)") (class "Default")
      (node (ref "D220") (pin "1") (pinfunction "A_1") (pintype "passive"))
      (node (ref "S220") (pin "1") (pinfunction "1_1") (pintype "passive"))
    )
    (net (code "40") (name "Net-(D221-A)") (class "Default")
      (node (ref "D221") (pin "1") (pinfunction "A_1") (pintype "passive"))
      (node (ref "S221") (pin "1") (pinfunction "1_1") (pintype "passive"))
    )
    (net (code "41") (name "Net-(D222-A)") (class "Default")
      (node (ref "D222") (pin "1") (pinfunction "A_1") (pintype "passive"))
      (node (ref "S222") (pin "1") (pinfunction "1_1") (pintype "passive"))
    )
    (net (code "42") (name "Net-(D223-A)") (class "Default")
      (node (ref "D223") (pin "1") (pinfunction "A_1") (pintype "passive"))
      (node (ref "S223") (pin "1") (pinfunction "1_1") (pintype "passive"))
    )
    (net (code "43") (name "Net-(D224-A)") (class "Default")
      (node (ref "D224") (pin "1") (pinfunction "A_1") (pintype "passive"))
      (node (ref "S224") (pin "1") (pinfunction "1_1") (pintype "passive"))
    )
    (net (code "44") (name "Net-(D225-A)") (class "Default")
      (node (ref "D225") (pin "1") (pinfunction "A_1") (pintype "passive"))
      (node (ref "S225") (pin "1") (pinfunction "1_1") (pintype "passive"))
    )
    (net (code "45") (name "Net-(D226-A)") (class "Default")
      (node (ref "D226") (pin "1") (pinfunction "A_1") (pintype "passive"))
      (node (ref "S226") (pin "1") (pinfunction "1_1") (pintype "passive"))
    )
    (net (code "46") (name "Net-(D227-A)") (class "Default")
      (node (ref "D227") (pin "1") (pinfunction "A_1") (pintype "passive"))
      (node (ref "S227") (pin "1") (pinfunction "1_1") (pintype "passive"))
    )
    (net (code "47") (name "Net-(D228-A)") (class "Default")
      (node (ref "D228") (pin "1") (pinfunction "A_1") (pintype "passive"))
      (node (ref "S228") (pin "1") (pinfunction "1_1") (pintype "passive"))
    )
    (net (code "48") (name "Net-(D229-A)") (class "Default")
      (node (ref "D229") (pin "1") (pinfunction "A_1") (pintype "passive"))
      (node (ref "S229") (pin "1") (pinfunction "1_1") (pintype "passive"))
    )
    (net (code "49") (name "Net-(D230-A)") (class "Default")
      (node (ref "D230") (pin "1") (pinfunction "A_1") (pintype "passive"))
      (node (ref "S230") (pin "1") (pinfunction "1_1") (pintype "passive"))
    )
    (net (code "50") (name "Net-(D231-A)") (class "Default")
      (node (ref "D231") (pin "1") (pinfunction "A_1") (pintype "passive"))
      (node (ref "S231") (pin "1") (pinfunction "1_1") (pintype "passive"))
    )
    (net (code "51") (name "Net-(D232-A)") (class "Default")
      (node (ref "D232") (pin "1") (pinfunction "A_1") (pintype "passive"))
      (node (ref "S232") (pin "1") (pinfunction "1_1") (pintype "passive"))
    )
    (net (code "52") (name "Net-(D233-A)") (class "Default")
      (node (ref "D233") (pin "1") (pinfunction "A_1") (pintype "passive"))
      (node (ref "S233") (pin "1") (pinfunction "1_1") (pintype "passive"))
    )
    (net (code "53") (name "Net-(D234-A)") (class "Default")
      (node (ref "D234") (pin "1") (pinfunction "A_1") (pintype "passive"))
      (node (ref "S234") (pin "1") (pinfunction "1_1") (pintype "passive"))
    )
    (net (code "54") (name "Net-(D235-A)") (class "Default")
      (node (ref "D235") (pin "1") (pinfunction "A_1") (pintype "passive"))
      (node (ref "S235") (pin "1") (pinfunction "1_1") (pintype "passive"))
    )
    (net (code "55") (name "Net-(D236-A)") (class "Default")
      (node (ref "D236") (pin "1") (pinfunction "A_1") (pintype "passive"))
      (node (ref "S236") (pin "1") (pinfunction "1_1") (pintype "passive"))
    )
    (net (code "56") (name "Net-(D237-A)") (class "Default")
      (node (ref "D237") (pin "1") (pinfunction "A_1") (pintype "passive"))
      (node (ref "S237") (pin "1") (pinfunction "1_1") (pintype "passive"))
    )
    (net (code "57") (name "Net-(D238-A)") (class "Default")
      (node (ref "D238") (pin "1") (pinfunction "A_1") (pintype "passive"))
      (node (ref "S238") (pin "1") (pinfunction "1_1") (pintype "passive"))
    )
    (net (code "58") (name "Net-(D239-A)") (class "Default")
      (node (ref "D239") (pin "1") (pinfunction "A_1") (pintype "passive"))
      (node (ref "S239") (pin "1") (pinfunction "1_1") (pintype "passive"))
    )
    (net (code "59") (name "Net-(D240-A)") (class "Default")
      (node (ref "D240") (pin "1") (pinfunction "A_1") (pintype "passive"))
      (node (ref "S240") (pin "1") (pinfunction "1_1") (pintype "passive"))
    )
    (net (code "60") (name "Net-(D241-A)") (class "Default")
      (node (ref "D241") (pin "1") (pinfunction "A_1") (pintype "passive"))
      (node (ref "S241") (pin "1") (pinfunction "1_1") (pintype "passive"))
    )
    (net (code "61") (name "Net-(D242-A)") (class "Default")
      (node (ref "D242") (pin "1") (pinfunction "A_1") (pintype "passive"))
      (node (ref "S242") (pin "1") (pinfunction "1_1") (pintype "passive"))
    )
    (net (code "62") (name "Net-(D243-A)") (class "Default")
      (node (ref "D243") (pin "1") (pinfunction "A_1") (pintype "passive"))
      (node (ref "S243") (pin "1") (pinfunction "1_1") (pintype "passive"))
    )
    (net (code "63") (name "Net-(D244-A)") (class "Default")
      (node (ref "D244") (pin "1") (pinfunction "A_1") (pintype "passive"))
      (node (ref "S244") (pin "1") (pinfunction "1_1") (pintype "passive"))
    )
    (net (code "64") (name "Net-(D245-A)") (class "Default")
      (node (ref "D245") (pin "1") (pinfunction "A_1") (pintype "passive"))
      (node (ref "S245") (pin "1") (pinfunction "1_1") (pintype "passive"))
    )
    (net (code "65") (name "Net-(D246-A)") (class "Default")
      (node (ref "D246") (pin "1") (pinfunction "A_1") (pintype "passive"))
      (node (ref "S246") (pin "1") (pinfunction "1_1") (pintype "passive"))
    )
    (net (code "66") (name "Net-(D247-A)") (class "Default")
      (node (ref "D247") (pin "1") (pinfunction "A_1") (pintype "passive"))
      (node (ref "S247") (pin "1") (pinfunction "1_1") (pintype "passive"))
    )
    (net (code "67") (name "Net-(D248-A)") (class "Default")
      (node (ref "D248") (pin "1") (pinfunction "A_1") (pintype "passive"))
      (node (ref "S248") (pin "1") (pinfunction "1_1") (pintype "passive"))
    )
    (net (code "68") (name "Net-(D249-A)") (class "Default")
      (node (ref "D249") (pin "1") (pinfunction "A_1") (pintype "passive"))
      (node (ref "S249") (pin "1") (pinfunction "1_1") (pintype "passive"))
    )
    (net (code "69") (name "Net-(D250-A)") (class "Default")
      (node (ref "D250") (pin "1") (pinfunction "A_1") (pintype "passive"))
      (node (ref "S250") (pin "1") (pinfunction "1_1") (pintype "passive"))
    )
    (net (code "70") (name "Net-(D251-A)") (class "Default")
      (node (ref "D251") (pin "1") (pinfunction "A_1") (pintype "passive"))
      (node (ref "S251") (pin "1") (pinfunction "1_1") (pintype "passive"))
    )
    (net (code "71") (name "Net-(D252-A)") (class "Default")
      (node (ref "D252") (pin "1") (pinfunction "A_1") (pintype "passive"))
      (node (ref "S252") (pin "1") (pinfunction "1_1") (pintype "passive"))
    )
    (net (code "72") (name "Net-(D253-A)") (class "Default")
      (node (ref "D253") (pin "1") (pinfunction "A_1") (pintype "passive"))
      (node (ref "S253") (pin "1") (pinfunction "1_1") (pintype "passive"))
    )
    (net (code "73") (name "Net-(D254-A)") (class "Default")
      (node (ref "D254") (pin "1") (pinfunction "A_1") (pintype "passive"))
      (node (ref "S254") (pin "1") (pinfunction "1_1") (pintype "passive"))
    )
    (net (code "74") (name "Net-(D255-A)") (class "Default")
      (node (ref "D255") (pin "1") (pinfunction "A_1") (pintype "passive"))
      (node (ref "S255") (pin "1") (pinfunction "1_1") (pintype "passive"))
    )
    (net (code "75") (name "Net-(D256-A)") (class "Default")
      (node (ref "D256") (pin "1") (pinfunction "A_1") (pintype "passive"))
      (node (ref "S256") (pin "1") (pinfunction "1_1") (pintype "passive"))
    )
    (net (code "76") (name "Net-(D257-A)") (class "Default")
      (node (ref "D257") (pin "1") (pinfunction "A_1") (pintype "passive"))
      (node (ref "S257") (pin "1") (pinfunction "1_1") (pintype "passive"))
    )
    (net (code "77") (name "Net-(D258-A)") (class "Default")
      (node (ref "D258") (pin "1") (pinfunction "A_1") (pintype "passive"))
      (node (ref "S258") (pin "1") (pinfunction "1_1") (pintype "passive"))
    )
    (net (code "78") (name "Net-(D259-A)") (class "Default")
      (node (ref "D259") (pin "1") (pinfunction "A_1") (pintype "passive"))
      (node (ref "S259") (pin "1") (pinfunction "1_1") (pintype "passive"))
    )
    (net (code "79") (name "Net-(D260-A)") (class "Default")
      (node (ref "D260") (pin "1") (pinfunction "A_1") (pintype "passive"))
      (node (ref "S260") (pin "1") (pinfunction "1_1") (pintype "passive"))
    )
    (net (code "80") (name "Net-(D261-A)") (class "Default")
      (node (ref "D261") (pin "1") (pinfunction "A_1") (pintype "passive"))
      (node (ref "S261") (pin "1") (pinfunction "1_1") (pintype "passive"))
    )
    (net (code "81") (name "Net-(D262-A)") (class "Default")
      (node (ref "D262") (pin "1") (pinfunction "A_1") (pintype "passive"))
      (node (ref "S262") (pin "1") (pinfunction "1_1") (pintype "passive"))
    )
    (net (code "82") (name "Net-(D263-A)") (class "Default")
      (node (ref "D263") (pin "1") (pinfunction "A_1") (pintype "passive"))
      (node (ref "S263") (pin "1") (pinfunction "1_1") (pintype "passive"))
    )
    (net (code "83") (name "Net-(D264-A)") (class "Default")
      (node (ref "D264") (pin "1") (pinfunction "A_1") (pintype "passive"))
      (node (ref "S264") (pin "1") (pinfunction "1_1") (pintype "passive"))
    )
    (net (code "84") (name "Net-(D265-A)") (class "Default")
      (node (ref "D265") (pin "1") (pinfunction "A_1") (pintype "passive"))
      (node (ref "S265") (pin "1") (pinfunction "1_1") (pintype "passive"))
    )
    (net (code "85") (name "Net-(D266-A)") (class "Default")
      (node (ref "D266") (pin "1") (pinfunction "A_1") (pintype "passive"))
      (node (ref "S266") (pin "1") (pinfunction "1_1") (pintype "passive"))
    )
    (net (code "86") (name "Net-(D267-A)") (class "Default")
      (node (ref "D267") (pin "1") (pinfunction "A_1") (pintype "passive"))
      (node (ref "S267") (pin "1") (pinfunction "1_1") (pintype "passive"))
    )
    (net (code "87") (name "Net-(D268-A)") (class "Default")
      (node (ref "D268") (pin "1") (pinfunction "A_1") (pintype "passive"))
      (node (ref "S268") (pin "1") (pinfunction "1_1") (pintype "passive"))
    )
    (net (code "88") (name "Net-(D269-A)") (class "Default")
      (node (ref "D269") (pin "1") (pinfunction "A_1") (pintype "passive"))
      (node (ref "S269") (pin "1") (pinfunction "1_1") (pintype "passive"))
    )
    (net (code "89") (name "Net-(D270-A)") (class "Default")
      (node (ref "D270") (pin "1") (pinfunction "A_1") (pintype "passive"))
      (node (ref "S270") (pin "1") (pinfunction "1_1") (pintype "passive"))
    )
  )
)
